# UsbA.net
KiCad netlist of a schematic drawn in EAGLE
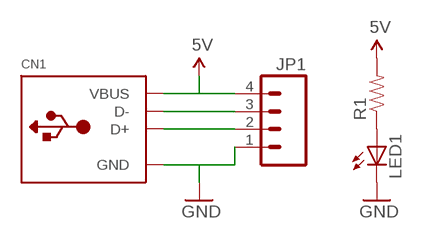
[diagram p0: schematic, sheet 1]

(export (version "E")
  (design (tool "Eeschema 10.0.6"))
  (components
    (comp (ref "CN1")
      (value "USB_TYPEAPCB")
      (footprint "eagle-import:USBA_PCB")
      (libsource (lib "eagle-import") (part "USB_TYPEAPCB"))
    )
    (comp (ref "JP1")
      (value "M04PTH")
      (footprint "eagle-import:1X04")
      (libsource (lib "eagle-import") (part "M04PTH"))
    )
    (comp (ref "LED1")
      (value "LED5MM")
      (footprint "eagle-import:LED5MM")
      (libsource (lib "eagle-import") (part "LED5MM"))
    )
    (comp (ref "R1")
      (value "RESISTORAXIAL-0.3")
      (footprint "eagle-import:AXIAL-0.3")
      (libsource (lib "eagle-import") (part "RESISTORAXIAL-0.3"))
    )
  )
  (nets
    (net (code "1") (name "5V") (class "Default")
      (node (ref "CN1") (pin "VCC") (pinfunction "VBUS_VCC") (pintype "power_in"))
      (node (ref "JP1") (pin "4") (pinfunction "4_4") (pintype "passive"))
      (node (ref "R1") (pin "P$2") (pinfunction "2_P$2") (pintype "passive"))
    )
    (net (code "2") (name "GND") (class "Default")
      (node (ref "CN1") (pin "GND") (pinfunction "GND_GND") (pintype "power_in"))
      (node (ref "JP1") (pin "1") (pinfunction "1_1") (pintype "passive"))
      (node (ref "LED1") (pin "K") (pinfunction "C_K") (pintype "passive"))
    )
    (net (code "3") (name "Net-(CN1-D+)") (class "Default")
      (node (ref "CN1") (pin "USB_PLUS") (pinfunction "D+_USB_PLUS") (pintype "bidirectional"))
      (node (ref "JP1") (pin "2") (pinfunction "2_2") (pintype "passive"))
    )
    (net (code "4") (name "Net-(CN1-D-)") (class "Default")
      (node (ref "CN1") (pin "USB_NEG") (pinfunction "D-_USB_NEG") (pintype "bidirectional"))
      (node (ref "JP1") (pin "3") (pinfunction "3_3") (pintype "passive"))
    )
    (net (code "5") (name "Net-(R1-1)") (class "Default")
      (node (ref "LED1") (pin "A") (pinfunction "A_A") (pintype "passive"))
      (node (ref "R1") (pin "P$1") (pinfunction "1_P$1") (pintype "passive"))
    )
  )
)
